# multiSPI_v21.net
KiCad netlist of a schematic drawn in EAGLE
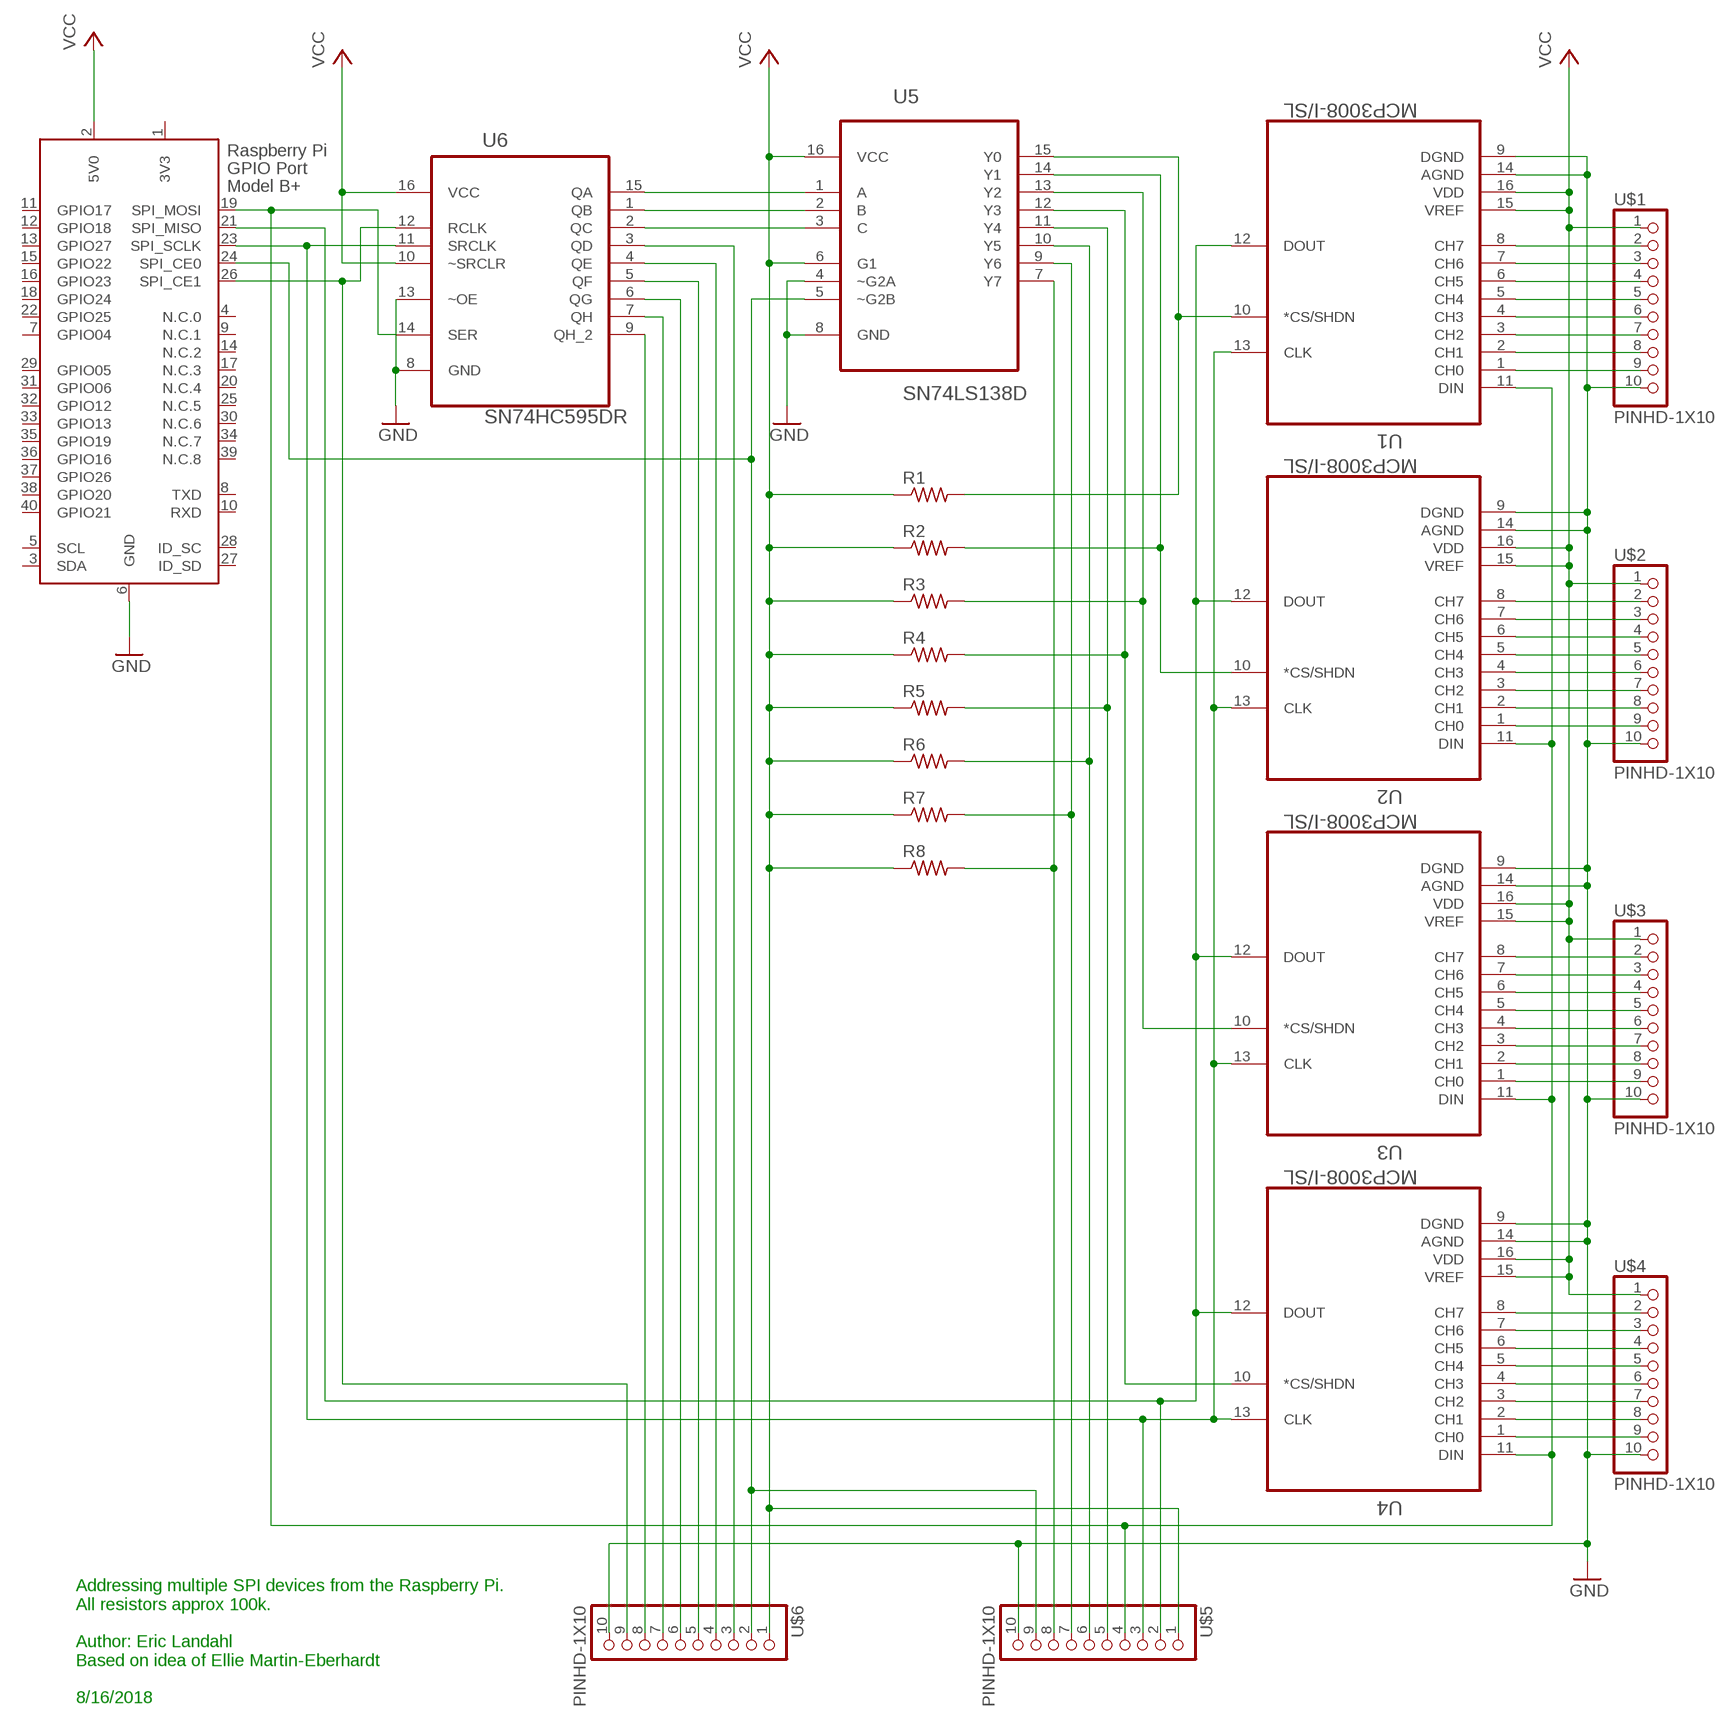
[diagram p0: schematic, sheet 1]

(export (version "E")
  (design (tool "Eeschema 10.0.6"))
  (components
    (comp (ref "R1")
      (value "R-US_R1210")
      (footprint "eagle-import:R1210")
      (libsource (lib "eagle-import") (part "R-US_R1210"))
    )
    (comp (ref "R2")
      (value "R-US_R1210")
      (footprint "eagle-import:R1210")
      (libsource (lib "eagle-import") (part "R-US_R1210"))
    )
    (comp (ref "R3")
      (value "R-US_R1210")
      (footprint "eagle-import:R1210")
      (libsource (lib "eagle-import") (part "R-US_R1210"))
    )
    (comp (ref "R4")
      (value "R-US_R1210")
      (footprint "eagle-import:R1210")
      (libsource (lib "eagle-import") (part "R-US_R1210"))
    )
    (comp (ref "R5")
      (value "R-US_R1210")
      (footprint "eagle-import:R1210")
      (libsource (lib "eagle-import") (part "R-US_R1210"))
    )
    (comp (ref "R6")
      (value "R-US_R1210")
      (footprint "eagle-import:R1210")
      (libsource (lib "eagle-import") (part "R-US_R1210"))
    )
    (comp (ref "R7")
      (value "R-US_R1210")
      (footprint "eagle-import:R1210")
      (libsource (lib "eagle-import") (part "R-US_R1210"))
    )
    (comp (ref "R8")
      (value "R-US_R1210")
      (footprint "eagle-import:R1210")
      (libsource (lib "eagle-import") (part "R-US_R1210"))
    )
    (comp (ref "U$1")
      (value "PINHD-1X10")
      (footprint "eagle-import:1X10-BIG")
      (libsource (lib "eagle-import") (part "PINHD-1X10"))
    )
    (comp (ref "U$2")
      (value "PINHD-1X10")
      (footprint "eagle-import:1X10-BIG")
      (libsource (lib "eagle-import") (part "PINHD-1X10"))
    )
    (comp (ref "U$3")
      (value "PINHD-1X10")
      (footprint "eagle-import:1X10-BIG")
      (libsource (lib "eagle-import") (part "PINHD-1X10"))
    )
    (comp (ref "U$4")
      (value "PINHD-1X10")
      (footprint "eagle-import:1X10-BIG")
      (libsource (lib "eagle-import") (part "PINHD-1X10"))
    )
    (comp (ref "U$5")
      (value "PINHD-1X10")
      (footprint "eagle-import:1X10-BIG")
      (libsource (lib "eagle-import") (part "PINHD-1X10"))
    )
    (comp (ref "U$6")
      (value "PINHD-1X10")
      (footprint "eagle-import:1X10-BIG")
      (libsource (lib "eagle-import") (part "PINHD-1X10"))
    )
    (comp (ref "U1")
      (value "MCP3008-I/SL")
      (footprint "eagle-import:SOIC127P600X175-16N")
      (libsource (lib "eagle-import") (part "MCP3008-I/SL"))
    )
    (comp (ref "U2")
      (value "MCP3008-I/SL")
      (footprint "eagle-import:SOIC127P600X175-16N")
      (fields (field (name "SPICEPREFIX") "X"))
      (libsource (lib "eagle-import") (part "MCP3008-I/SL"))
    )
    (comp (ref "U3")
      (value "MCP3008-I/SL")
      (footprint "eagle-import:SOIC127P600X175-16N")
      (fields (field (name "SPICEPREFIX") "X"))
      (libsource (lib "eagle-import") (part "MCP3008-I/SL"))
    )
    (comp (ref "U4")
      (value "MCP3008-I/SL")
      (footprint "eagle-import:SOIC127P600X175-16N")
      (libsource (lib "eagle-import") (part "MCP3008-I/SL"))
    )
    (comp (ref "U5")
      (value "SN74LS138D")
      (footprint "eagle-import:SOIC127P600X175-16N")
      (libsource (lib "eagle-import") (part "SN74LS138D"))
    )
    (comp (ref "U6")
      (value "SN74HC595DR")
      (footprint "eagle-import:SOIC127P600X175-16N")
      (fields (field (name "SPICEPREFIX") "X"))
      (libsource (lib "eagle-import") (part "SN74HC595DR"))
    )
    (comp (ref "X1")
      (value "RASPI_GPIO_B+_BOX")
      (footprint "eagle-import:RASPI_GPIO_B+_BOX")
      (libsource (lib "eagle-import") (part "RASPI_GPIO_B+_BOX"))
    )
  )
  (nets
    (net (code "1") (name "/3V3") (class "Default")
      (node (ref "X1") (pin "1") (pinfunction "3V3_1") (pintype "power_in"))
    )
    (net (code "2") (name "GND") (class "Default")
      (node (ref "U$1") (pin "10") (pinfunction "10_10") (pintype "passive"))
      (node (ref "U$2") (pin "10") (pinfunction "10_10") (pintype "passive"))
      (node (ref "U$3") (pin "10") (pinfunction "10_10") (pintype "passive"))
      (node (ref "U$4") (pin "10") (pinfunction "10_10") (pintype "passive"))
      (node (ref "U$5") (pin "10") (pinfunction "10_10") (pintype "passive"))
      (node (ref "U$6") (pin "10") (pinfunction "10_10") (pintype "passive"))
      (node (ref "U1") (pin "14") (pinfunction "AGND_14") (pintype "passive"))
      (node (ref "U1") (pin "9") (pinfunction "DGND_9") (pintype "passive"))
      (node (ref "U2") (pin "14") (pinfunction "AGND_14") (pintype "passive"))
      (node (ref "U2") (pin "9") (pinfunction "DGND_9") (pintype "passive"))
      (node (ref "U3") (pin "14") (pinfunction "AGND_14") (pintype "passive"))
      (node (ref "U3") (pin "9") (pinfunction "DGND_9") (pintype "passive"))
      (node (ref "U4") (pin "14") (pinfunction "AGND_14") (pintype "passive"))
      (node (ref "U4") (pin "9") (pinfunction "DGND_9") (pintype "passive"))
      (node (ref "U5") (pin "4") (pinfunction "~{G2A}_4") (pintype "input"))
      (node (ref "U5") (pin "8") (pinfunction "GND_8") (pintype "passive"))
      (node (ref "U6") (pin "13") (pinfunction "~{OE}_13") (pintype "input"))
      (node (ref "U6") (pin "8") (pinfunction "GND_8") (pintype "passive"))
      (node (ref "X1") (pin "6") (pinfunction "GND_6") (pintype "power_in"))
    )
    (net (code "3") (name "Net-(U1-*CS{slash}SHDN)") (class "Default")
      (node (ref "R1") (pin "2") (pinfunction "2_2") (pintype "passive"))
      (node (ref "U1") (pin "10") (pinfunction "*CS/SHDN_10") (pintype "input"))
      (node (ref "U5") (pin "15") (pinfunction "Y0_15") (pintype "output"))
    )
    (net (code "4") (name "Net-(U1-CH0)") (class "Default")
      (node (ref "U$1") (pin "9") (pinfunction "9_9") (pintype "passive"))
      (node (ref "U1") (pin "1") (pinfunction "CH0_1") (pintype "input"))
    )
    (net (code "5") (name "Net-(U1-CH1)") (class "Default")
      (node (ref "U$1") (pin "8") (pinfunction "8_8") (pintype "passive"))
      (node (ref "U1") (pin "2") (pinfunction "CH1_2") (pintype "input"))
    )
    (net (code "6") (name "Net-(U1-CH2)") (class "Default")
      (node (ref "U$1") (pin "7") (pinfunction "7_7") (pintype "passive"))
      (node (ref "U1") (pin "3") (pinfunction "CH2_3") (pintype "input"))
    )
    (net (code "7") (name "Net-(U1-CH3)") (class "Default")
      (node (ref "U$1") (pin "6") (pinfunction "6_6") (pintype "passive"))
      (node (ref "U1") (pin "4") (pinfunction "CH3_4") (pintype "input"))
    )
    (net (code "8") (name "Net-(U1-CH4)") (class "Default")
      (node (ref "U$1") (pin "5") (pinfunction "5_5") (pintype "passive"))
      (node (ref "U1") (pin "5") (pinfunction "CH4_5") (pintype "input"))
    )
    (net (code "9") (name "Net-(U1-CH5)") (class "Default")
      (node (ref "U$1") (pin "4") (pinfunction "4_4") (pintype "passive"))
      (node (ref "U1") (pin "6") (pinfunction "CH5_6") (pintype "input"))
    )
    (net (code "10") (name "Net-(U1-CH6)") (class "Default")
      (node (ref "U$1") (pin "3") (pinfunction "3_3") (pintype "passive"))
      (node (ref "U1") (pin "7") (pinfunction "CH6_7") (pintype "input"))
    )
    (net (code "11") (name "Net-(U1-CH7)") (class "Default")
      (node (ref "U$1") (pin "2") (pinfunction "2_2") (pintype "passive"))
      (node (ref "U1") (pin "8") (pinfunction "CH7_8") (pintype "input"))
    )
    (net (code "12") (name "Net-(U1-CLK)") (class "Default")
      (node (ref "U$5") (pin "3") (pinfunction "3_3") (pintype "passive"))
      (node (ref "U1") (pin "13") (pinfunction "CLK_13") (pintype "input"))
      (node (ref "U2") (pin "13") (pinfunction "CLK_13") (pintype "input"))
      (node (ref "U3") (pin "13") (pinfunction "CLK_13") (pintype "input"))
      (node (ref "U4") (pin "13") (pinfunction "CLK_13") (pintype "input"))
      (node (ref "U6") (pin "11") (pinfunction "SRCLK_11") (pintype "input"))
      (node (ref "X1") (pin "23") (pinfunction "SPI_SCLK_23") (pintype "bidirectional"))
    )
    (net (code "13") (name "Net-(U1-DIN)") (class "Default")
      (node (ref "U$5") (pin "4") (pinfunction "4_4") (pintype "passive"))
      (node (ref "U1") (pin "11") (pinfunction "DIN_11") (pintype "input"))
      (node (ref "U2") (pin "11") (pinfunction "DIN_11") (pintype "input"))
      (node (ref "U3") (pin "11") (pinfunction "DIN_11") (pintype "input"))
      (node (ref "U4") (pin "11") (pinfunction "DIN_11") (pintype "input"))
      (node (ref "U6") (pin "14") (pinfunction "SER_14") (pintype "input"))
      (node (ref "X1") (pin "19") (pinfunction "SPI_MOSI_19") (pintype "bidirectional"))
    )
    (net (code "14") (name "Net-(U1-DOUT)") (class "Default")
      (node (ref "U$5") (pin "2") (pinfunction "2_2") (pintype "passive"))
      (node (ref "U1") (pin "12") (pinfunction "DOUT_12") (pintype "output"))
      (node (ref "U2") (pin "12") (pinfunction "DOUT_12") (pintype "output"))
      (node (ref "U3") (pin "12") (pinfunction "DOUT_12") (pintype "output"))
      (node (ref "U4") (pin "12") (pinfunction "DOUT_12") (pintype "output"))
      (node (ref "X1") (pin "21") (pinfunction "SPI_MISO_21") (pintype "bidirectional"))
    )
    (net (code "15") (name "Net-(U2-*CS{slash}SHDN)") (class "Default")
      (node (ref "R2") (pin "2") (pinfunction "2_2") (pintype "passive"))
      (node (ref "U2") (pin "10") (pinfunction "*CS/SHDN_10") (pintype "input"))
      (node (ref "U5") (pin "14") (pinfunction "Y1_14") (pintype "output"))
    )
    (net (code "16") (name "Net-(U2-CH0)") (class "Default")
      (node (ref "U$2") (pin "9") (pinfunction "9_9") (pintype "passive"))
      (node (ref "U2") (pin "1") (pinfunction "CH0_1") (pintype "input"))
    )
    (net (code "17") (name "Net-(U2-CH1)") (class "Default")
      (node (ref "U$2") (pin "8") (pinfunction "8_8") (pintype "passive"))
      (node (ref "U2") (pin "2") (pinfunction "CH1_2") (pintype "input"))
    )
    (net (code "18") (name "Net-(U2-CH2)") (class "Default")
      (node (ref "U$2") (pin "7") (pinfunction "7_7") (pintype "passive"))
      (node (ref "U2") (pin "3") (pinfunction "CH2_3") (pintype "input"))
    )
    (net (code "19") (name "Net-(U2-CH3)") (class "Default")
      (node (ref "U$2") (pin "6") (pinfunction "6_6") (pintype "passive"))
      (node (ref "U2") (pin "4") (pinfunction "CH3_4") (pintype "input"))
    )
    (net (code "20") (name "Net-(U2-CH4)") (class "Default")
      (node (ref "U$2") (pin "5") (pinfunction "5_5") (pintype "passive"))
      (node (ref "U2") (pin "5") (pinfunction "CH4_5") (pintype "input"))
    )
    (net (code "21") (name "Net-(U2-CH5)") (class "Default")
      (node (ref "U$2") (pin "4") (pinfunction "4_4") (pintype "passive"))
      (node (ref "U2") (pin "6") (pinfunction "CH5_6") (pintype "input"))
    )
    (net (code "22") (name "Net-(U2-CH6)") (class "Default")
      (node (ref "U$2") (pin "3") (pinfunction "3_3") (pintype "passive"))
      (node (ref "U2") (pin "7") (pinfunction "CH6_7") (pintype "input"))
    )
    (net (code "23") (name "Net-(U2-CH7)") (class "Default")
      (node (ref "U$2") (pin "2") (pinfunction "2_2") (pintype "passive"))
      (node (ref "U2") (pin "8") (pinfunction "CH7_8") (pintype "input"))
    )
    (net (code "24") (name "Net-(U3-*CS{slash}SHDN)") (class "Default")
      (node (ref "R3") (pin "2") (pinfunction "2_2") (pintype "passive"))
      (node (ref "U3") (pin "10") (pinfunction "*CS/SHDN_10") (pintype "input"))
      (node (ref "U5") (pin "13") (pinfunction "Y2_13") (pintype "output"))
    )
    (net (code "25") (name "Net-(U3-CH0)") (class "Default")
      (node (ref "U$3") (pin "9") (pinfunction "9_9") (pintype "passive"))
      (node (ref "U3") (pin "1") (pinfunction "CH0_1") (pintype "input"))
    )
    (net (code "26") (name "Net-(U3-CH1)") (class "Default")
      (node (ref "U$3") (pin "8") (pinfunction "8_8") (pintype "passive"))
      (node (ref "U3") (pin "2") (pinfunction "CH1_2") (pintype "input"))
    )
    (net (code "27") (name "Net-(U3-CH2)") (class "Default")
      (node (ref "U$3") (pin "7") (pinfunction "7_7") (pintype "passive"))
      (node (ref "U3") (pin "3") (pinfunction "CH2_3") (pintype "input"))
    )
    (net (code "28") (name "Net-(U3-CH3)") (class "Default")
      (node (ref "U$3") (pin "6") (pinfunction "6_6") (pintype "passive"))
      (node (ref "U3") (pin "4") (pinfunction "CH3_4") (pintype "input"))
    )
    (net (code "29") (name "Net-(U3-CH4)") (class "Default")
      (node (ref "U$3") (pin "5") (pinfunction "5_5") (pintype "passive"))
      (node (ref "U3") (pin "5") (pinfunction "CH4_5") (pintype "input"))
    )
    (net (code "30") (name "Net-(U3-CH5)") (class "Default")
      (node (ref "U$3") (pin "4") (pinfunction "4_4") (pintype "passive"))
      (node (ref "U3") (pin "6") (pinfunction "CH5_6") (pintype "input"))
    )
    (net (code "31") (name "Net-(U3-CH6)") (class "Default")
      (node (ref "U$3") (pin "3") (pinfunction "3_3") (pintype "passive"))
      (node (ref "U3") (pin "7") (pinfunction "CH6_7") (pintype "input"))
    )
    (net (code "32") (name "Net-(U3-CH7)") (class "Default")
      (node (ref "U$3") (pin "2") (pinfunction "2_2") (pintype "passive"))
      (node (ref "U3") (pin "8") (pinfunction "CH7_8") (pintype "input"))
    )
    (net (code "33") (name "Net-(U4-*CS{slash}SHDN)") (class "Default")
      (node (ref "R4") (pin "2") (pinfunction "2_2") (pintype "passive"))
      (node (ref "U4") (pin "10") (pinfunction "*CS/SHDN_10") (pintype "input"))
      (node (ref "U5") (pin "12") (pinfunction "Y3_12") (pintype "output"))
    )
    (net (code "34") (name "Net-(U4-CH0)") (class "Default")
      (node (ref "U$4") (pin "9") (pinfunction "9_9") (pintype "passive"))
      (node (ref "U4") (pin "1") (pinfunction "CH0_1") (pintype "input"))
    )
    (net (code "35") (name "Net-(U4-CH1)") (class "Default")
      (node (ref "U$4") (pin "8") (pinfunction "8_8") (pintype "passive"))
      (node (ref "U4") (pin "2") (pinfunction "CH1_2") (pintype "input"))
    )
    (net (code "36") (name "Net-(U4-CH2)") (class "Default")
      (node (ref "U$4") (pin "7") (pinfunction "7_7") (pintype "passive"))
      (node (ref "U4") (pin "3") (pinfunction "CH2_3") (pintype "input"))
    )
    (net (code "37") (name "Net-(U4-CH3)") (class "Default")
      (node (ref "U$4") (pin "6") (pinfunction "6_6") (pintype "passive"))
      (node (ref "U4") (pin "4") (pinfunction "CH3_4") (pintype "input"))
    )
    (net (code "38") (name "Net-(U4-CH4)") (class "Default")
      (node (ref "U$4") (pin "5") (pinfunction "5_5") (pintype "passive"))
      (node (ref "U4") (pin "5") (pinfunction "CH4_5") (pintype "input"))
    )
    (net (code "39") (name "Net-(U4-CH5)") (class "Default")
      (node (ref "U$4") (pin "4") (pinfunction "4_4") (pintype "passive"))
      (node (ref "U4") (pin "6") (pinfunction "CH5_6") (pintype "input"))
    )
    (net (code "40") (name "Net-(U4-CH6)") (class "Default")
      (node (ref "U$4") (pin "3") (pinfunction "3_3") (pintype "passive"))
      (node (ref "U4") (pin "7") (pinfunction "CH6_7") (pintype "input"))
    )
    (net (code "41") (name "Net-(U4-CH7)") (class "Default")
      (node (ref "U$4") (pin "2") (pinfunction "2_2") (pintype "passive"))
      (node (ref "U4") (pin "8") (pinfunction "CH7_8") (pintype "input"))
    )
    (net (code "42") (name "Net-(U5-A)") (class "Default")
      (node (ref "U5") (pin "1") (pinfunction "A_1") (pintype "input"))
      (node (ref "U6") (pin "15") (pinfunction "QA_15") (pintype "output"))
    )
    (net (code "43") (name "Net-(U5-B)") (class "Default")
      (node (ref "U5") (pin "2") (pinfunction "B_2") (pintype "input"))
      (node (ref "U6") (pin "1") (pinfunction "QB_1") (pintype "output"))
    )
    (net (code "44") (name "Net-(U5-C)") (class "Default")
      (node (ref "U5") (pin "3") (pinfunction "C_3") (pintype "input"))
      (node (ref "U6") (pin "2") (pinfunction "QC_2") (pintype "output"))
    )
    (net (code "45") (name "Net-(U5-Y4)") (class "Default")
      (node (ref "R5") (pin "2") (pinfunction "2_2") (pintype "passive"))
      (node (ref "U$5") (pin "5") (pinfunction "5_5") (pintype "passive"))
      (node (ref "U5") (pin "11") (pinfunction "Y4_11") (pintype "output"))
    )
    (net (code "46") (name "Net-(U5-Y5)") (class "Default")
      (node (ref "R6") (pin "2") (pinfunction "2_2") (pintype "passive"))
      (node (ref "U$5") (pin "6") (pinfunction "6_6") (pintype "passive"))
      (node (ref "U5") (pin "10") (pinfunction "Y5_10") (pintype "output"))
    )
    (net (code "47") (name "Net-(U5-Y6)") (class "Default")
      (node (ref "R7") (pin "2") (pinfunction "2_2") (pintype "passive"))
      (node (ref "U$5") (pin "7") (pinfunction "7_7") (pintype "passive"))
      (node (ref "U5") (pin "9") (pinfunction "Y6_9") (pintype "output"))
    )
    (net (code "48") (name "Net-(U5-Y7)") (class "Default")
      (node (ref "R8") (pin "2") (pinfunction "2_2") (pintype "passive"))
      (node (ref "U$5") (pin "8") (pinfunction "8_8") (pintype "passive"))
      (node (ref "U5") (pin "7") (pinfunction "Y7_7") (pintype "output"))
    )
    (net (code "49") (name "Net-(U5-~{G2B})") (class "Default")
      (node (ref "U$5") (pin "9") (pinfunction "9_9") (pintype "passive"))
      (node (ref "U$6") (pin "2") (pinfunction "2_2") (pintype "passive"))
      (node (ref "U5") (pin "5") (pinfunction "~{G2B}_5") (pintype "input"))
      (node (ref "X1") (pin "24") (pinfunction "SPI_CE0_24") (pintype "bidirectional"))
    )
    (net (code "50") (name "Net-(U6-QD)") (class "Default")
      (node (ref "U$6") (pin "3") (pinfunction "3_3") (pintype "passive"))
      (node (ref "U6") (pin "3") (pinfunction "QD_3") (pintype "output"))
    )
    (net (code "51") (name "Net-(U6-QE)") (class "Default")
      (node (ref "U$6") (pin "4") (pinfunction "4_4") (pintype "passive"))
      (node (ref "U6") (pin "4") (pinfunction "QE_4") (pintype "output"))
    )
    (net (code "52") (name "Net-(U6-QF)") (class "Default")
      (node (ref "U$6") (pin "5") (pinfunction "5_5") (pintype "passive"))
      (node (ref "U6") (pin "5") (pinfunction "QF_5") (pintype "output"))
    )
    (net (code "53") (name "Net-(U6-QG)") (class "Default")
      (node (ref "U$6") (pin "6") (pinfunction "6_6") (pintype "passive"))
      (node (ref "U6") (pin "6") (pinfunction "QG_6") (pintype "output"))
    )
    (net (code "54") (name "Net-(U6-QH)") (class "Default")
      (node (ref "U$6") (pin "7") (pinfunction "7_7") (pintype "passive"))
      (node (ref "U6") (pin "7") (pinfunction "QH_7") (pintype "output"))
    )
    (net (code "55") (name "Net-(U6-QH_2)") (class "Default")
      (node (ref "U$6") (pin "8") (pinfunction "8_8") (pintype "passive"))
      (node (ref "U6") (pin "9") (pinfunction "QH_2_9") (pintype "output"))
    )
    (net (code "56") (name "Net-(U6-RCLK)") (class "Default")
      (node (ref "U$6") (pin "9") (pinfunction "9_9") (pintype "passive"))
      (node (ref "U6") (pin "12") (pinfunction "RCLK_12") (pintype "input"))
      (node (ref "X1") (pin "26") (pinfunction "SPI_CE1_26") (pintype "bidirectional"))
    )
    (net (code "57") (name "VCC") (class "Default")
      (node (ref "R1") (pin "1") (pinfunction "1_1") (pintype "passive"))
      (node (ref "R2") (pin "1") (pinfunction "1_1") (pintype "passive"))
      (node (ref "R3") (pin "1") (pinfunction "1_1") (pintype "passive"))
      (node (ref "R4") (pin "1") (pinfunction "1_1") (pintype "passive"))
      (node (ref "R5") (pin "1") (pinfunction "1_1") (pintype "passive"))
      (node (ref "R6") (pin "1") (pinfunction "1_1") (pintype "passive"))
      (node (ref "R7") (pin "1") (pinfunction "1_1") (pintype "passive"))
      (node (ref "R8") (pin "1") (pinfunction "1_1") (pintype "passive"))
      (node (ref "U$1") (pin "1") (pinfunction "1_1") (pintype "passive"))
      (node (ref "U$2") (pin "1") (pinfunction "1_1") (pintype "passive"))
      (node (ref "U$3") (pin "1") (pinfunction "1_1") (pintype "passive"))
      (node (ref "U$4") (pin "1") (pinfunction "1_1") (pintype "passive"))
      (node (ref "U$5") (pin "1") (pinfunction "1_1") (pintype "passive"))
      (node (ref "U$6") (pin "1") (pinfunction "1_1") (pintype "passive"))
      (node (ref "U1") (pin "15") (pinfunction "VREF_15") (pintype "input"))
      (node (ref "U1") (pin "16") (pinfunction "VDD_16") (pintype "power_in"))
      (node (ref "U2") (pin "15") (pinfunction "VREF_15") (pintype "input"))
      (node (ref "U2") (pin "16") (pinfunction "VDD_16") (pintype "power_in"))
      (node (ref "U3") (pin "15") (pinfunction "VREF_15") (pintype "input"))
      (node (ref "U3") (pin "16") (pinfunction "VDD_16") (pintype "power_in"))
      (node (ref "U4") (pin "15") (pinfunction "VREF_15") (pintype "input"))
      (node (ref "U4") (pin "16") (pinfunction "VDD_16") (pintype "power_in"))
      (node (ref "U5") (pin "16") (pinfunction "VCC_16") (pintype "power_in"))
      (node (ref "U5") (pin "6") (pinfunction "G1_6") (pintype "input"))
      (node (ref "U6") (pin "10") (pinfunction "~{SRCLR}_10") (pintype "input"))
      (node (ref "U6") (pin "16") (pinfunction "VCC_16") (pintype "power_in"))
      (node (ref "X1") (pin "2") (pinfunction "5V0_2") (pintype "power_in"))
    )
    (net (code "58") (name "unconnected-(X1-GPIO04-Pad7)") (class "Default")
      (node (ref "X1") (pin "7") (pinfunction "GPIO04_7") (pintype "bidirectional"))
    )
    (net (code "59") (name "unconnected-(X1-GPIO05-Pad29)") (class "Default")
      (node (ref "X1") (pin "29") (pinfunction "GPIO05_29") (pintype "no_connect"))
    )
    (net (code "60") (name "unconnected-(X1-GPIO06-Pad31)") (class "Default")
      (node (ref "X1") (pin "31") (pinfunction "GPIO06_31") (pintype "no_connect"))
    )
    (net (code "61") (name "unconnected-(X1-GPIO12-Pad32)") (class "Default")
      (node (ref "X1") (pin "32") (pinfunction "GPIO12_32") (pintype "no_connect"))
    )
    (net (code "62") (name "unconnected-(X1-GPIO13-Pad33)") (class "Default")
      (node (ref "X1") (pin "33") (pinfunction "GPIO13_33") (pintype "no_connect"))
    )
    (net (code "63") (name "unconnected-(X1-GPIO16-Pad36)") (class "Default")
      (node (ref "X1") (pin "36") (pinfunction "GPIO16_36") (pintype "no_connect"))
    )
    (net (code "64") (name "unconnected-(X1-GPIO17-Pad11)") (class "Default")
      (node (ref "X1") (pin "11") (pinfunction "GPIO17_11") (pintype "bidirectional"))
    )
    (net (code "65") (name "unconnected-(X1-GPIO18-Pad12)") (class "Default")
      (node (ref "X1") (pin "12") (pinfunction "GPIO18_12") (pintype "bidirectional"))
    )
    (net (code "66") (name "unconnected-(X1-GPIO19-Pad35)") (class "Default")
      (node (ref "X1") (pin "35") (pinfunction "GPIO19_35") (pintype "no_connect"))
    )
    (net (code "67") (name "unconnected-(X1-GPIO20-Pad38)") (class "Default")
      (node (ref "X1") (pin "38") (pinfunction "GPIO20_38") (pintype "no_connect"))
    )
    (net (code "68") (name "unconnected-(X1-GPIO21-Pad40)") (class "Default")
      (node (ref "X1") (pin "40") (pinfunction "GPIO21_40") (pintype "no_connect"))
    )
    (net (code "69") (name "unconnected-(X1-GPIO22-Pad15)") (class "Default")
      (node (ref "X1") (pin "15") (pinfunction "GPIO22_15") (pintype "bidirectional"))
    )
    (net (code "70") (name "unconnected-(X1-GPIO23-Pad16)") (class "Default")
      (node (ref "X1") (pin "16") (pinfunction "GPIO23_16") (pintype "bidirectional"))
    )
    (net (code "71") (name "unconnected-(X1-GPIO24-Pad18)") (class "Default")
      (node (ref "X1") (pin "18") (pinfunction "GPIO24_18") (pintype "bidirectional"))
    )
    (net (code "72") (name "unconnected-(X1-GPIO25-Pad22)") (class "Default")
      (node (ref "X1") (pin "22") (pinfunction "GPIO25_22") (pintype "bidirectional"))
    )
    (net (code "73") (name "unconnected-(X1-GPIO26-Pad37)") (class "Default")
      (node (ref "X1") (pin "37") (pinfunction "GPIO26_37") (pintype "no_connect"))
    )
    (net (code "74") (name "unconnected-(X1-GPIO27-Pad13)") (class "Default")
      (node (ref "X1") (pin "13") (pinfunction "GPIO27_13") (pintype "bidirectional"))
    )
    (net (code "75") (name "unconnected-(X1-ID_SC-Pad28)") (class "Default")
      (node (ref "X1") (pin "28") (pinfunction "ID_SC_28") (pintype "no_connect"))
    )
    (net (code "76") (name "unconnected-(X1-ID_SD-Pad27)") (class "Default")
      (node (ref "X1") (pin "27") (pinfunction "ID_SD_27") (pintype "no_connect"))
    )
    (net (code "77") (name "unconnected-(X1-N.C.0-Pad4)") (class "Default")
      (node (ref "X1") (pin "4") (pinfunction "N.C.0_4") (pintype "no_connect"))
    )
    (net (code "78") (name "unconnected-(X1-N.C.1-Pad9)") (class "Default")
      (node (ref "X1") (pin "9") (pinfunction "N.C.1_9") (pintype "no_connect"))
    )
    (net (code "79") (name "unconnected-(X1-N.C.2-Pad14)") (class "Default")
      (node (ref "X1") (pin "14") (pinfunction "N.C.2_14") (pintype "no_connect"))
    )
    (net (code "80") (name "unconnected-(X1-N.C.3-Pad17)") (class "Default")
      (node (ref "X1") (pin "17") (pinfunction "N.C.3_17") (pintype "no_connect"))
    )
    (net (code "81") (name "unconnected-(X1-N.C.4-Pad20)") (class "Default")
      (node (ref "X1") (pin "20") (pinfunction "N.C.4_20") (pintype "no_connect"))
    )
    (net (code "82") (name "unconnected-(X1-N.C.5-Pad25)") (class "Default")
      (node (ref "X1") (pin "25") (pinfunction "N.C.5_25") (pintype "no_connect"))
    )
    (net (code "83") (name "unconnected-(X1-N.C.6-Pad30)") (class "Default")
      (node (ref "X1") (pin "30") (pinfunction "N.C.6_30") (pintype "no_connect"))
    )
    (net (code "84") (name "unconnected-(X1-N.C.7-Pad34)") (class "Default")
      (node (ref "X1") (pin "34") (pinfunction "N.C.7_34") (pintype "no_connect"))
    )
    (net (code "85") (name "unconnected-(X1-N.C.8-Pad39)") (class "Default")
      (node (ref "X1") (pin "39") (pinfunction "N.C.8_39") (pintype "no_connect"))
    )
    (net (code "86") (name "unconnected-(X1-RXD-Pad10)") (class "Default")
      (node (ref "X1") (pin "10") (pinfunction "RXD_10") (pintype "bidirectional"))
    )
    (net (code "87") (name "unconnected-(X1-SCL-Pad5)") (class "Default")
      (node (ref "X1") (pin "5") (pinfunction "SCL_5") (pintype "bidirectional"))
    )
    (net (code "88") (name "unconnected-(X1-SDA-Pad3)") (class "Default")
      (node (ref "X1") (pin "3") (pinfunction "SDA_3") (pintype "bidirectional"))
    )
    (net (code "89") (name "unconnected-(X1-TXD-Pad8)") (class "Default")
      (node (ref "X1") (pin "8") (pinfunction "TXD_8") (pintype "bidirectional"))
    )
  )
)
